# Control.net
KiCad netlist of a schematic drawn in Altium Designer
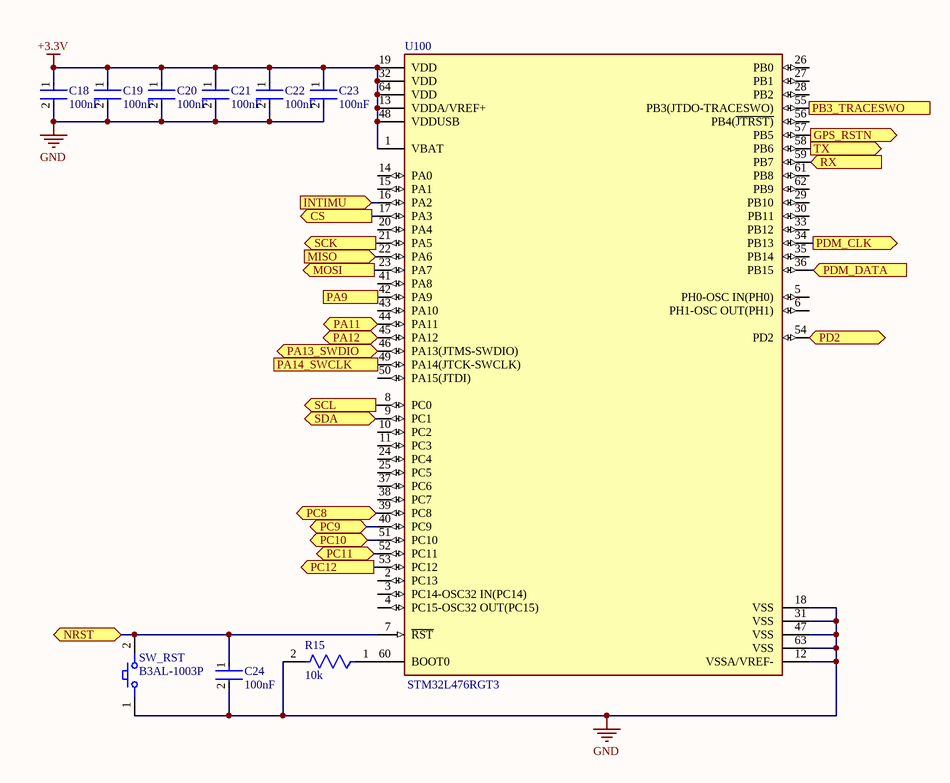
[diagram p0: Control.SchDoc]

(export (version "E")
  (design (tool "Eeschema 10.0.6"))
  (components
    (comp (ref "C18")
      (value "100nF")
      (footprint "FP-GCG188-0_2-IPC_B")
      (libsource (lib "Altium Content Vault") (part "02cd4be3c70576c341d710602a673aa"))
    )
    (comp (ref "C19")
      (value "100nF")
      (footprint "FP-GCG188-0_2-IPC_B")
      (libsource (lib "Altium Content Vault") (part "02cd4be3c70576c341d710602a673aa"))
    )
    (comp (ref "C20")
      (value "100nF")
      (footprint "FP-GCG188-0_2-IPC_B")
      (libsource (lib "Altium Content Vault") (part "02cd4be3c70576c341d710602a673aa"))
    )
    (comp (ref "C21")
      (value "100nF")
      (footprint "FP-GCG188-0_2-IPC_B")
      (libsource (lib "Altium Content Vault") (part "02cd4be3c70576c341d710602a673aa"))
    )
    (comp (ref "C22")
      (value "100nF")
      (footprint "FP-GCG188-0_2-IPC_B")
      (libsource (lib "Altium Content Vault") (part "02cd4be3c70576c341d710602a673aa"))
    )
    (comp (ref "C23")
      (value "100nF")
      (footprint "FP-GCG188-0_2-IPC_B")
      (libsource (lib "Altium Content Vault") (part "02cd4be3c70576c341d710602a673aa"))
    )
    (comp (ref "C24")
      (value "100nF")
      (footprint "FP-GCG188-0_2-IPC_B")
      (libsource (lib "Altium Content Vault") (part "02cd4be3c70576c341d710602a673aa"))
    )
    (comp (ref "R15")
      (value "10k")
      (footprint "FP-CRCW0603-HPe3-MFG")
      (description "RES SMD 10K OHM 1% 1/3W 0603")
      (fields (field (name "TOLERANCE") "1%"))
      (libsource (lib "Altium Content Vault") (part "1029c3af85768c4190bb7ad29bc67b5"))
    )
    (comp (ref "SW_RST")
      (value "B3AL-1003P")
      (footprint "FP-B3AL-1003P-MFG")
      (description "SWITCH TACTILE SPST-NO 0.05A 16V")
      (libsource (lib "Altium Content Vault") (part "69e8347f6a24c021ef43a914a4df441"))
    )
    (comp (ref "U100")
      (value "STM32L476RGT3")
      (footprint "FP-LQFP64-5W-IPC_C")
      (description "IC MCU 32BIT 1MB FLASH 64LQFP")
      (libsource (lib "Altium Content Vault") (part "74cda0a56cc221a62fcf3ef167a0dda"))
    )
  )
  (nets
    (net (code "1") (name "+3.3V") (class "Default")
      (node (ref "C18") (pin "1") (pinfunction "1_1") (pintype "passive"))
      (node (ref "C19") (pin "1") (pinfunction "1_1") (pintype "passive"))
      (node (ref "C20") (pin "1") (pinfunction "1_1") (pintype "passive"))
      (node (ref "C21") (pin "1") (pinfunction "1_1") (pintype "passive"))
      (node (ref "C22") (pin "1") (pinfunction "1_1") (pintype "passive"))
      (node (ref "C23") (pin "1") (pinfunction "1_1") (pintype "passive"))
      (node (ref "U100") (pin "1") (pinfunction "VBAT_1") (pintype "power_in"))
      (node (ref "U100") (pin "13") (pinfunction "VDDA/VREF+_13") (pintype "power_in"))
      (node (ref "U100") (pin "19") (pinfunction "VDD_19") (pintype "power_in"))
      (node (ref "U100") (pin "32") (pinfunction "VDD_32") (pintype "power_in"))
      (node (ref "U100") (pin "48") (pinfunction "VDDUSB_48") (pintype "power_in"))
      (node (ref "U100") (pin "64") (pinfunction "VDD_64") (pintype "power_in"))
    )
    (net (code "2") (name "/CS") (class "Default")
      (node (ref "U100") (pin "17") (pinfunction "PA3_17") (pintype "bidirectional"))
    )
    (net (code "3") (name "/GPS_RSTN") (class "Default")
      (node (ref "U100") (pin "57") (pinfunction "PB5_57") (pintype "bidirectional"))
    )
    (net (code "4") (name "/INTIMU") (class "Default")
      (node (ref "U100") (pin "16") (pinfunction "PA2_16") (pintype "bidirectional"))
    )
    (net (code "5") (name "/MISO") (class "Default")
      (node (ref "U100") (pin "22") (pinfunction "PA6_22") (pintype "bidirectional"))
    )
    (net (code "6") (name "/MOSI") (class "Default")
      (node (ref "U100") (pin "23") (pinfunction "PA7_23") (pintype "bidirectional"))
    )
    (net (code "7") (name "/NRST") (class "Default")
      (node (ref "C24") (pin "1") (pinfunction "1_1") (pintype "passive"))
      (node (ref "SW_RST") (pin "2") (pinfunction "2_2") (pintype "passive"))
      (node (ref "U100") (pin "7") (pinfunction "~{RST}_7") (pintype "input"))
    )
    (net (code "8") (name "/PA9") (class "Default")
      (node (ref "U100") (pin "42") (pinfunction "PA9_42") (pintype "bidirectional"))
    )
    (net (code "9") (name "/PA11") (class "Default")
      (node (ref "U100") (pin "44") (pinfunction "PA11_44") (pintype "bidirectional"))
    )
    (net (code "10") (name "/PA12") (class "Default")
      (node (ref "U100") (pin "45") (pinfunction "PA12_45") (pintype "bidirectional"))
    )
    (net (code "11") (name "/PA13_SWDIO") (class "Default")
      (node (ref "U100") (pin "46") (pinfunction "PA13(JTMS-SWDIO)_46") (pintype "bidirectional"))
    )
    (net (code "12") (name "/PA14_SWCLK") (class "Default")
      (node (ref "U100") (pin "49") (pinfunction "PA14(JTCK-SWCLK)_49") (pintype "bidirectional"))
    )
    (net (code "13") (name "/PB3_TRACESWO") (class "Default")
      (node (ref "U100") (pin "55") (pinfunction "PB3(JTDO-TRACESWO)_55") (pintype "bidirectional"))
    )
    (net (code "14") (name "/PC8") (class "Default")
      (node (ref "U100") (pin "39") (pinfunction "PC8_39") (pintype "bidirectional"))
    )
    (net (code "15") (name "/PC9") (class "Default")
      (node (ref "U100") (pin "40") (pinfunction "PC9_40") (pintype "bidirectional"))
    )
    (net (code "16") (name "/PC10") (class "Default")
      (node (ref "U100") (pin "51") (pinfunction "PC10_51") (pintype "bidirectional"))
    )
    (net (code "17") (name "/PC11") (class "Default")
      (node (ref "U100") (pin "52") (pinfunction "PC11_52") (pintype "bidirectional"))
    )
    (net (code "18") (name "/PC12") (class "Default")
      (node (ref "U100") (pin "53") (pinfunction "PC12_53") (pintype "bidirectional"))
    )
    (net (code "19") (name "/PD2") (class "Default")
      (node (ref "U100") (pin "54") (pinfunction "PD2_54") (pintype "bidirectional"))
    )
    (net (code "20") (name "/PDM_CLK") (class "Default")
      (node (ref "U100") (pin "34") (pinfunction "PB13_34") (pintype "bidirectional"))
    )
    (net (code "21") (name "/PDM_DATA") (class "Default")
      (node (ref "U100") (pin "36") (pinfunction "PB15_36") (pintype "bidirectional"))
    )
    (net (code "22") (name "/RX") (class "Default")
      (node (ref "U100") (pin "59") (pinfunction "PB7_59") (pintype "bidirectional"))
    )
    (net (code "23") (name "/SCK") (class "Default")
      (node (ref "U100") (pin "21") (pinfunction "PA5_21") (pintype "bidirectional"))
    )
    (net (code "24") (name "/SCL") (class "Default")
      (node (ref "U100") (pin "8") (pinfunction "PC0_8") (pintype "bidirectional"))
    )
    (net (code "25") (name "/SDA") (class "Default")
      (node (ref "U100") (pin "9") (pinfunction "PC1_9") (pintype "bidirectional"))
    )
    (net (code "26") (name "/TX") (class "Default")
      (node (ref "U100") (pin "58") (pinfunction "PB6_58") (pintype "bidirectional"))
    )
    (net (code "27") (name "GND") (class "Default")
      (node (ref "C18") (pin "2") (pinfunction "2_2") (pintype "passive"))
      (node (ref "C19") (pin "2") (pinfunction "2_2") (pintype "passive"))
      (node (ref "C20") (pin "2") (pinfunction "2_2") (pintype "passive"))
      (node (ref "C21") (pin "2") (pinfunction "2_2") (pintype "passive"))
      (node (ref "C22") (pin "2") (pinfunction "2_2") (pintype "passive"))
      (node (ref "C23") (pin "2") (pinfunction "2_2") (pintype "passive"))
      (node (ref "C24") (pin "2") (pinfunction "2_2") (pintype "passive"))
      (node (ref "R15") (pin "2") (pinfunction "2_2") (pintype "passive"))
      (node (ref "SW_RST") (pin "1") (pinfunction "1_1") (pintype "passive"))
      (node (ref "U100") (pin "12") (pinfunction "VSSA/VREF-_12") (pintype "power_in"))
      (node (ref "U100") (pin "18") (pinfunction "VSS_18") (pintype "power_in"))
      (node (ref "U100") (pin "31") (pinfunction "VSS_31") (pintype "power_in"))
      (node (ref "U100") (pin "47") (pinfunction "VSS_47") (pintype "power_in"))
      (node (ref "U100") (pin "63") (pinfunction "VSS_63") (pintype "power_in"))
    )
    (net (code "28") (name "Net-(U100-BOOT0)") (class "Default")
      (node (ref "R15") (pin "1") (pinfunction "1_1") (pintype "passive"))
      (node (ref "U100") (pin "60") (pinfunction "BOOT0_60") (pintype "passive"))
    )
    (net (code "29") (name "unconnected-(U100-PA0-Pad14)") (class "Default")
      (node (ref "U100") (pin "14") (pinfunction "PA0_14") (pintype "bidirectional"))
    )
    (net (code "30") (name "unconnected-(U100-PA1-Pad15)") (class "Default")
      (node (ref "U100") (pin "15") (pinfunction "PA1_15") (pintype "bidirectional"))
    )
    (net (code "31") (name "unconnected-(U100-PA4-Pad20)") (class "Default")
      (node (ref "U100") (pin "20") (pinfunction "PA4_20") (pintype "bidirectional"))
    )
    (net (code "32") (name "unconnected-(U100-PA8-Pad41)") (class "Default")
      (node (ref "U100") (pin "41") (pinfunction "PA8_41") (pintype "bidirectional"))
    )
    (net (code "33") (name "unconnected-(U100-PA10-Pad43)") (class "Default")
      (node (ref "U100") (pin "43") (pinfunction "PA10_43") (pintype "bidirectional"))
    )
    (net (code "34") (name "unconnected-(U100-PA15(JTDI)-Pad50)") (class "Default")
      (node (ref "U100") (pin "50") (pinfunction "PA15(JTDI)_50") (pintype "bidirectional"))
    )
    (net (code "35") (name "unconnected-(U100-PB0-Pad26)") (class "Default")
      (node (ref "U100") (pin "26") (pinfunction "PB0_26") (pintype "bidirectional"))
    )
    (net (code "36") (name "unconnected-(U100-PB1-Pad27)") (class "Default")
      (node (ref "U100") (pin "27") (pinfunction "PB1_27") (pintype "bidirectional"))
    )
    (net (code "37") (name "unconnected-(U100-PB2-Pad28)") (class "Default")
      (node (ref "U100") (pin "28") (pinfunction "PB2_28") (pintype "bidirectional"))
    )
    (net (code "38") (name "unconnected-(U100-PB4(~{JTRST)}-Pad56)") (class "Default")
      (node (ref "U100") (pin "56") (pinfunction "PB4(~{JTRST)}_56") (pintype "bidirectional"))
    )
    (net (code "39") (name "unconnected-(U100-PB8-Pad61)") (class "Default")
      (node (ref "U100") (pin "61") (pinfunction "PB8_61") (pintype "bidirectional"))
    )
    (net (code "40") (name "unconnected-(U100-PB9-Pad62)") (class "Default")
      (node (ref "U100") (pin "62") (pinfunction "PB9_62") (pintype "bidirectional"))
    )
    (net (code "41") (name "unconnected-(U100-PB10-Pad29)") (class "Default")
      (node (ref "U100") (pin "29") (pinfunction "PB10_29") (pintype "bidirectional"))
    )
    (net (code "42") (name "unconnected-(U100-PB11-Pad30)") (class "Default")
      (node (ref "U100") (pin "30") (pinfunction "PB11_30") (pintype "bidirectional"))
    )
    (net (code "43") (name "unconnected-(U100-PB12-Pad33)") (class "Default")
      (node (ref "U100") (pin "33") (pinfunction "PB12_33") (pintype "bidirectional"))
    )
    (net (code "44") (name "unconnected-(U100-PB14-Pad35)") (class "Default")
      (node (ref "U100") (pin "35") (pinfunction "PB14_35") (pintype "bidirectional"))
    )
    (net (code "45") (name "unconnected-(U100-PC2-Pad10)") (class "Default")
      (node (ref "U100") (pin "10") (pinfunction "PC2_10") (pintype "bidirectional"))
    )
    (net (code "46") (name "unconnected-(U100-PC3-Pad11)") (class "Default")
      (node (ref "U100") (pin "11") (pinfunction "PC3_11") (pintype "bidirectional"))
    )
    (net (code "47") (name "unconnected-(U100-PC4-Pad24)") (class "Default")
      (node (ref "U100") (pin "24") (pinfunction "PC4_24") (pintype "bidirectional"))
    )
    (net (code "48") (name "unconnected-(U100-PC5-Pad25)") (class "Default")
      (node (ref "U100") (pin "25") (pinfunction "PC5_25") (pintype "bidirectional"))
    )
    (net (code "49") (name "unconnected-(U100-PC6-Pad37)") (class "Default")
      (node (ref "U100") (pin "37") (pinfunction "PC6_37") (pintype "bidirectional"))
    )
    (net (code "50") (name "unconnected-(U100-PC7-Pad38)") (class "Default")
      (node (ref "U100") (pin "38") (pinfunction "PC7_38") (pintype "bidirectional"))
    )
    (net (code "51") (name "unconnected-(U100-PC13-Pad2)") (class "Default")
      (node (ref "U100") (pin "2") (pinfunction "PC13_2") (pintype "bidirectional"))
    )
    (net (code "52") (name "unconnected-(U100-PC14-OSC32_IN(PC14)-Pad3)") (class "Default")
      (node (ref "U100") (pin "3") (pinfunction "PC14-OSC32_IN(PC14)_3") (pintype "bidirectional"))
    )
    (net (code "53") (name "unconnected-(U100-PC15-OSC32_OUT(PC15)-Pad4)") (class "Default")
      (node (ref "U100") (pin "4") (pinfunction "PC15-OSC32_OUT(PC15)_4") (pintype "bidirectional"))
    )
    (net (code "54") (name "unconnected-(U100-PH0-OSC_IN(PH0)-Pad5)") (class "Default")
      (node (ref "U100") (pin "5") (pinfunction "PH0-OSC_IN(PH0)_5") (pintype "bidirectional"))
    )
    (net (code "55") (name "unconnected-(U100-PH1-OSC_OUT(PH1)-Pad6)") (class "Default")
      (node (ref "U100") (pin "6") (pinfunction "PH1-OSC_OUT(PH1)_6") (pintype "bidirectional"))
    )
  )
)
